# ESP32-S3-WROOM-1_Breakout.net
KiCad netlist of a schematic drawn in EasyEDA Pro
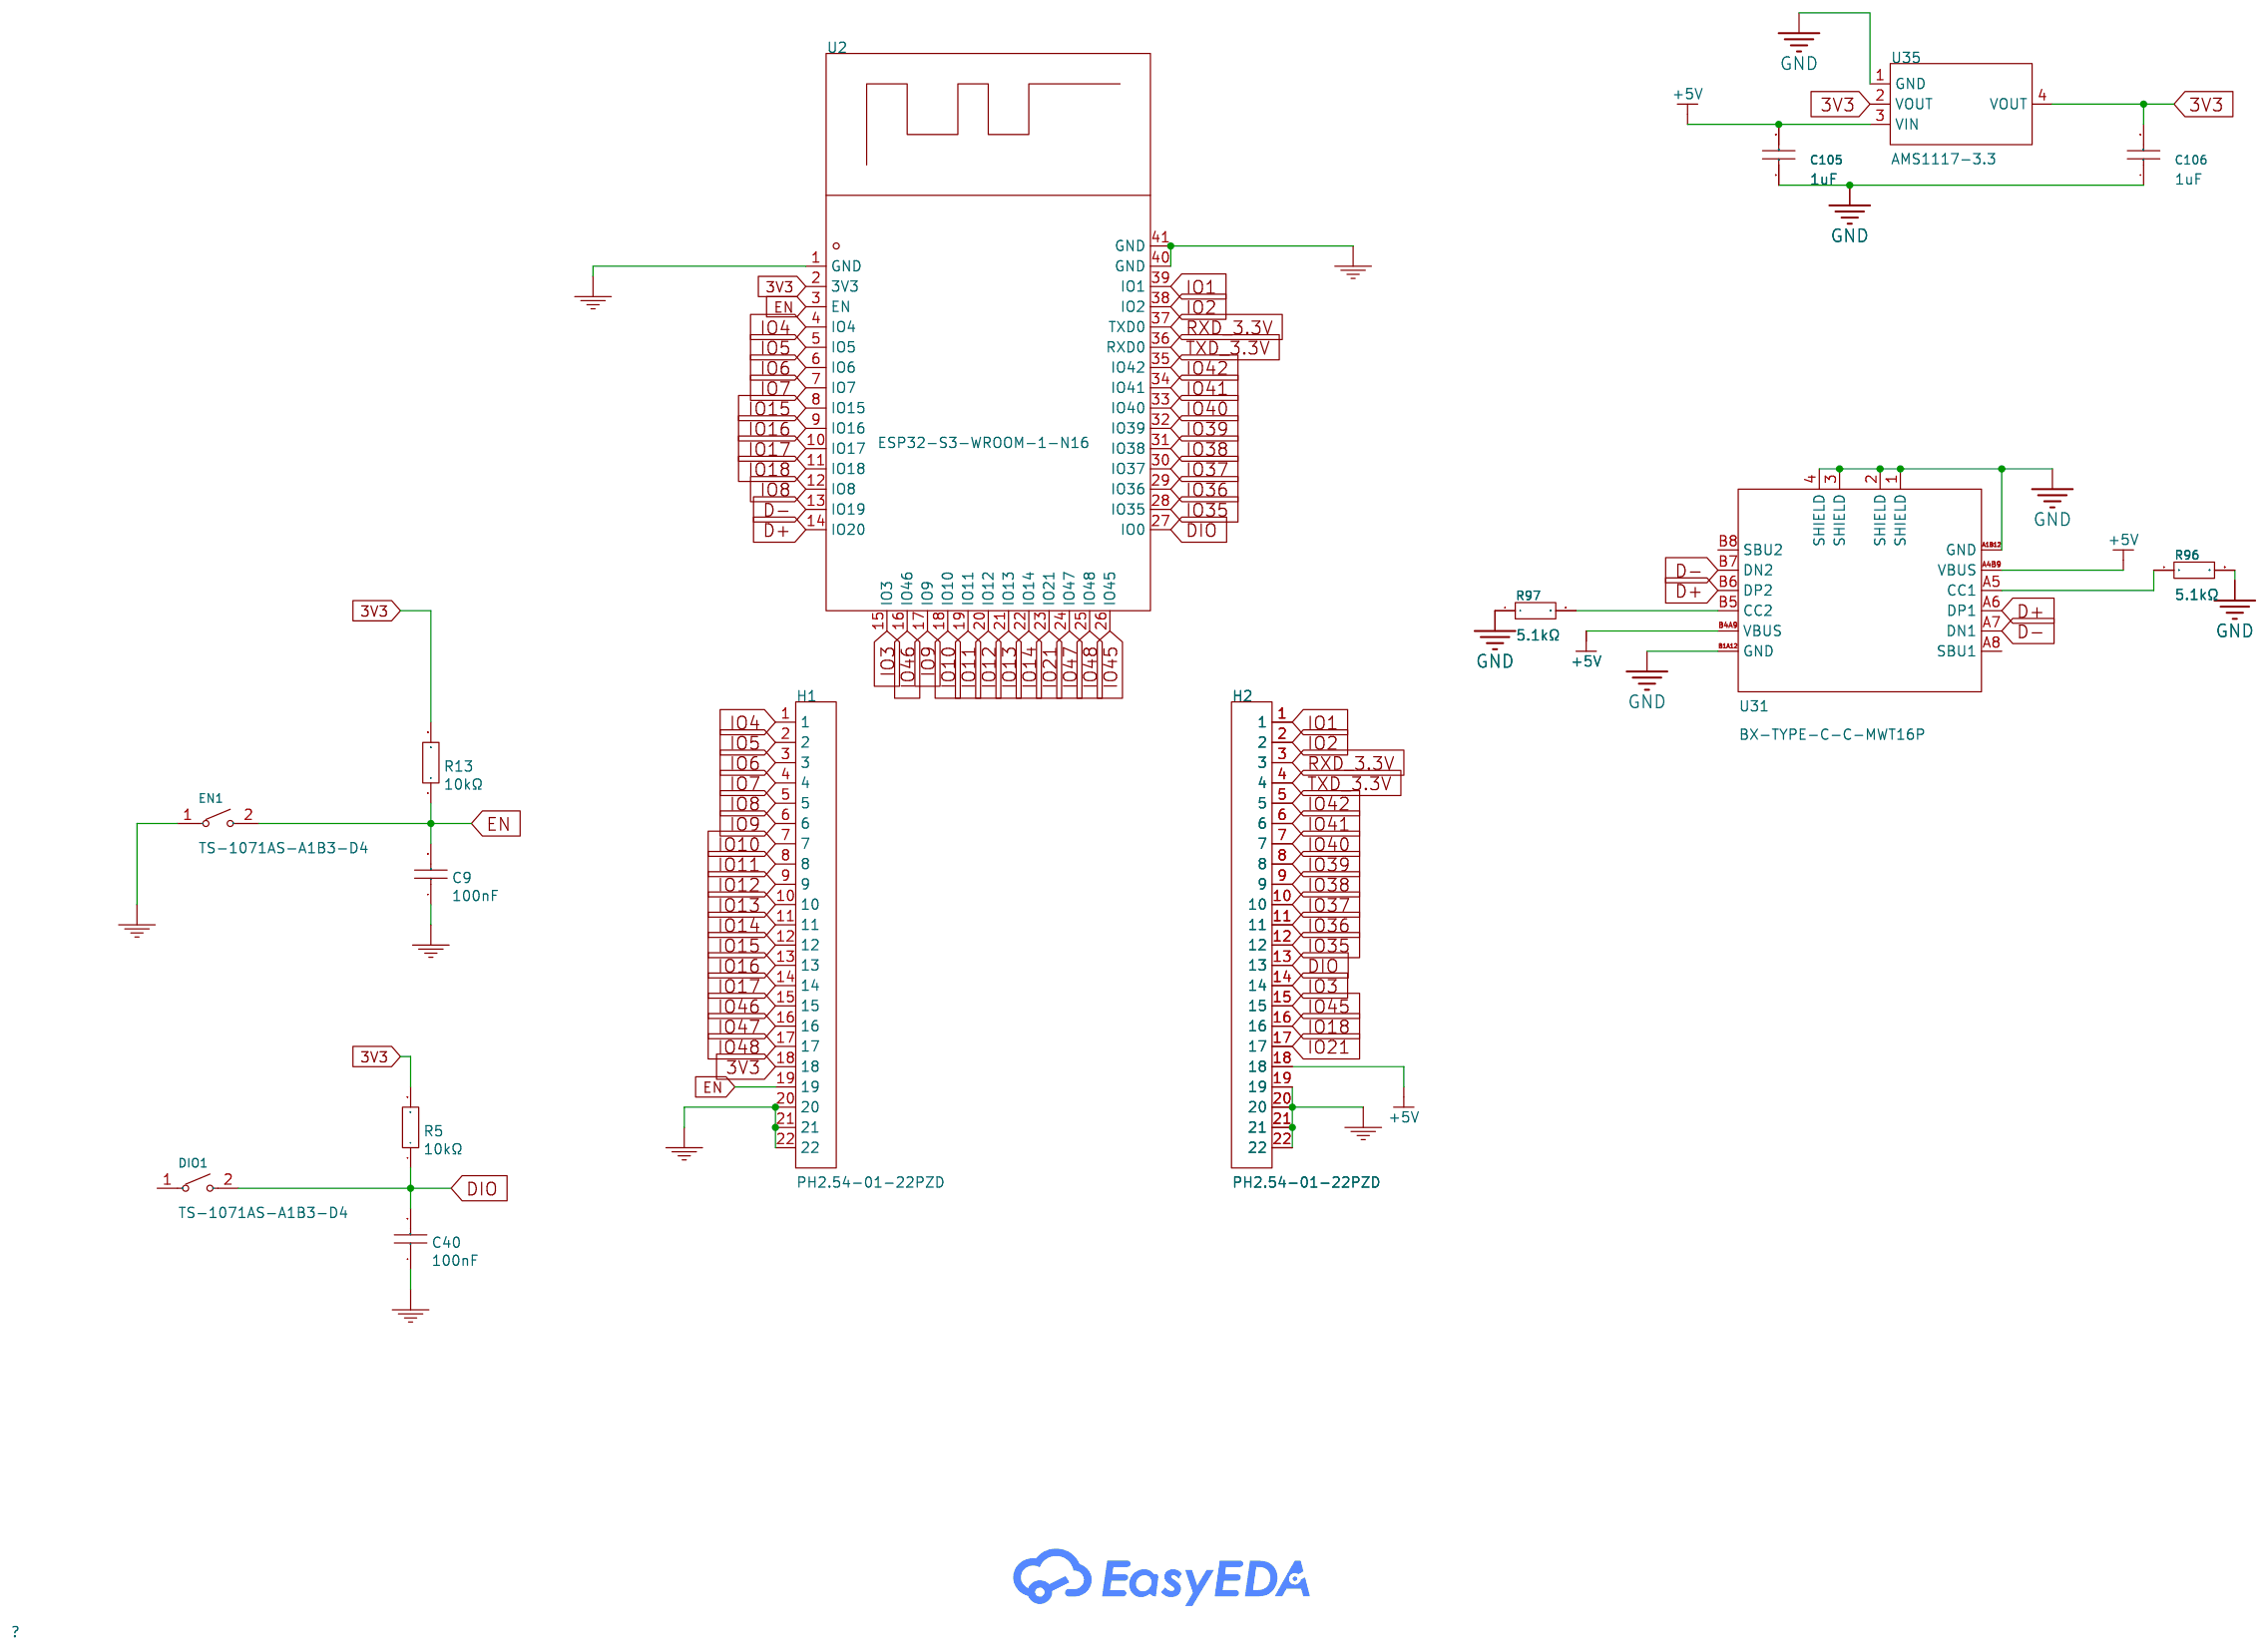
[diagram p0: schematic sheet]

(export (version "E")
  (design (tool "Eeschema 10.0.6"))
  (components
    (comp (ref "C9")
      (value "100nF")
      (footprint "easyedapro:C0402_NEW")
      (fields (field (name "Manufacturer Part") "CL05B104KO5NNNC") (field (name "Manufacturer") "SAMSUNG"))
      (libsource (lib "easyedapro") (part "100nF"))
    )
    (comp (ref "C40")
      (value "100nF")
      (footprint "easyedapro:C0402_NEW")
      (fields (field (name "Manufacturer Part") "CL05B104KO5NNNC") (field (name "Manufacturer") "SAMSUNG"))
      (libsource (lib "easyedapro") (part "100nF"))
    )
    (comp (ref "C105")
      (value "1uF")
      (footprint "easyedapro:C0402")
      (fields
        (field (name "Manufacturer Part") "CL05A105KP5NNNC")
        (field (name "Manufacturer") "SAMSUNG(三星)")
      )
      (libsource (lib "easyedapro") (part "CL05A105KP5NNNC"))
    )
    (comp (ref "C106")
      (value "1uF")
      (footprint "easyedapro:C0402")
      (fields
        (field (name "Manufacturer Part") "CL05A105KP5NNNC")
        (field (name "Manufacturer") "SAMSUNG(三星)")
      )
      (libsource (lib "easyedapro") (part "CL05A105KP5NNNC"))
    )
    (comp (ref "DIO1")
      (value "TS-1071AS-A1B3-D4")
      (footprint "easyedapro:SW-SMD_L4.0-W3.0-LS4.8")
      (fields (field (name "Manufacturer") "Yuandi(元迪)"))
      (libsource (lib "easyedapro") (part "TS-1071AS-A1B3-D4"))
    )
    (comp (ref "EN1")
      (value "TS-1071AS-A1B3-D4")
      (footprint "easyedapro:SW-SMD_L4.0-W3.0-LS4.8")
      (fields (field (name "Manufacturer") "Yuandi(元迪)"))
      (libsource (lib "easyedapro") (part "TS-1071AS-A1B3-D4"))
    )
    (comp (ref "H1")
      (value "PH2.54-01-22PZD")
      (footprint "easyedapro:HDR-TH_PH2.54-01-22PZD")
      (fields (field (name "Manufacturer") "XUNPU(讯普)"))
      (libsource (lib "easyedapro") (part "PH2.54-01-22PZD"))
    )
    (comp (ref "H2")
      (value "PH2.54-01-22PZD")
      (footprint "easyedapro:HDR-TH_PH2.54-01-22PZD")
      (fields (field (name "Manufacturer") "XUNPU(讯普)"))
      (libsource (lib "easyedapro") (part "PH2.54-01-22PZD"))
    )
    (comp (ref "R5")
      (value "10kΩ")
      (footprint "easyedapro:R0402")
      (fields (field (name "Manufacturer Part") "0402WGF1002TCE") (field (name "Manufacturer") "UniOhm"))
      (libsource (lib "easyedapro") (part "10kΩ"))
    )
    (comp (ref "R13")
      (value "10kΩ")
      (footprint "easyedapro:R0402")
      (fields (field (name "Manufacturer Part") "0402WGF1002TCE") (field (name "Manufacturer") "UniOhm"))
      (libsource (lib "easyedapro") (part "10kΩ"))
    )
    (comp (ref "R96")
      (value "5.1kΩ")
      (footprint "easyedapro:R0402")
      (fields
        (field (name "Manufacturer Part") "0402WGF5101TCE")
        (field (name "Manufacturer") "UNI-ROYAL(厚声)")
      )
      (libsource (lib "easyedapro") (part "0402WGF5101TCE"))
    )
    (comp (ref "R97")
      (value "5.1kΩ")
      (footprint "easyedapro:R0402")
      (fields
        (field (name "Manufacturer Part") "0402WGF5101TCE")
        (field (name "Manufacturer") "UNI-ROYAL(厚声)")
      )
      (libsource (lib "easyedapro") (part "0402WGF5101TCE"))
    )
    (comp (ref "U2")
      (value "ESP32-S3-WROOM-1-N16")
      (footprint "easyedapro:WIRELM-SMD_ESP32-S3-WROOM-1")
      (fields (field (name "Manufacturer") "ESPRESSIF(乐鑫)"))
      (libsource (lib "easyedapro") (part "ESP32-S3-WROOM-1(N16)"))
    )
    (comp (ref "U31")
      (value "BX-TYPE-C-C-MWT16P")
      (footprint "easyedapro:USB-C-SMD_BX-TYPE-C-C-MWT16P")
      (fields (field (name "Manufacturer") "Bossie(博锡)"))
      (libsource (lib "easyedapro") (part "BX-TYPE-C-C-MWT16P"))
    )
    (comp (ref "U35")
      (value "AMS1117-3.3")
      (footprint "easyedapro:SOT-223-3_L6.5-W3.4-P2.30-LS7.0-BR")
      (fields (field (name "Manufacturer") "AMS"))
      (libsource (lib "easyedapro") (part "AMS1117-3.3"))
    )
  )
  (nets
    (net (code "1") (name "+5V") (class "Default")
      (node (ref "C105") (pin "2") (pinfunction "2_2") (pintype "input"))
      (node (ref "H2") (pin "18") (pinfunction "18_18") (pintype "unspecified"))
      (node (ref "U31") (pin "A4B9") (pinfunction "VBUS_A4B9") (pintype "unspecified"))
      (node (ref "U31") (pin "B4A9") (pinfunction "VBUS_B4A9") (pintype "unspecified"))
      (node (ref "U35") (pin "3") (pinfunction "VIN_3") (pintype "unspecified"))
    )
    (net (code "2") (name "3V3") (class "Default")
      (node (ref "C106") (pin "2") (pinfunction "2_2") (pintype "input"))
      (node (ref "H1") (pin "18") (pinfunction "18_18") (pintype "unspecified"))
      (node (ref "R13") (pin "2") (pinfunction "2_2") (pintype "input"))
      (node (ref "R5") (pin "2") (pinfunction "2_2") (pintype "input"))
      (node (ref "U2") (pin "2") (pinfunction "3V3_2") (pintype "unspecified"))
      (node (ref "U35") (pin "2") (pinfunction "VOUT_2") (pintype "unspecified"))
      (node (ref "U35") (pin "4") (pinfunction "VOUT_4") (pintype "unspecified"))
    )
    (net (code "3") (name "D+") (class "Default")
      (node (ref "U2") (pin "14") (pinfunction "IO20_14") (pintype "unspecified"))
      (node (ref "U31") (pin "A6") (pinfunction "DP1_A6") (pintype "unspecified"))
      (node (ref "U31") (pin "B6") (pinfunction "DP2_B6") (pintype "unspecified"))
    )
    (net (code "4") (name "D-") (class "Default")
      (node (ref "U2") (pin "13") (pinfunction "IO19_13") (pintype "unspecified"))
      (node (ref "U31") (pin "A7") (pinfunction "DN1_A7") (pintype "unspecified"))
      (node (ref "U31") (pin "B7") (pinfunction "DN2_B7") (pintype "unspecified"))
    )
    (net (code "5") (name "DIO") (class "Default")
      (node (ref "C40") (pin "2") (pinfunction "2_2") (pintype "input"))
      (node (ref "DIO1") (pin "2") (pinfunction "2_2") (pintype "input"))
      (node (ref "H2") (pin "13") (pinfunction "13_13") (pintype "unspecified"))
      (node (ref "R5") (pin "1") (pinfunction "1_1") (pintype "input"))
      (node (ref "U2") (pin "27") (pinfunction "IO0_27") (pintype "unspecified"))
    )
    (net (code "6") (name "EN") (class "Default")
      (node (ref "C9") (pin "2") (pinfunction "2_2") (pintype "input"))
      (node (ref "EN1") (pin "2") (pinfunction "2_2") (pintype "input"))
      (node (ref "H1") (pin "19") (pinfunction "19_19") (pintype "unspecified"))
      (node (ref "R13") (pin "1") (pinfunction "1_1") (pintype "input"))
      (node (ref "U2") (pin "3") (pinfunction "EN_3") (pintype "unspecified"))
    )
    (net (code "7") (name "GND") (class "Default")
      (node (ref "C105") (pin "1") (pinfunction "1_1") (pintype "input"))
      (node (ref "C106") (pin "1") (pinfunction "1_1") (pintype "input"))
      (node (ref "C40") (pin "1") (pinfunction "1_1") (pintype "input"))
      (node (ref "C9") (pin "1") (pinfunction "1_1") (pintype "input"))
      (node (ref "EN1") (pin "1") (pinfunction "1_1") (pintype "input"))
      (node (ref "H1") (pin "20") (pinfunction "20_20") (pintype "unspecified"))
      (node (ref "H1") (pin "21") (pinfunction "21_21") (pintype "unspecified"))
      (node (ref "H1") (pin "22") (pinfunction "22_22") (pintype "unspecified"))
      (node (ref "H2") (pin "19") (pinfunction "19_19") (pintype "unspecified"))
      (node (ref "H2") (pin "20") (pinfunction "20_20") (pintype "unspecified"))
      (node (ref "H2") (pin "21") (pinfunction "21_21") (pintype "unspecified"))
      (node (ref "H2") (pin "22") (pinfunction "22_22") (pintype "unspecified"))
      (node (ref "R96") (pin "2") (pinfunction "2_2") (pintype "input"))
      (node (ref "R97") (pin "1") (pinfunction "1_1") (pintype "input"))
      (node (ref "U2") (pin "1") (pinfunction "GND_1") (pintype "unspecified"))
      (node (ref "U2") (pin "40") (pinfunction "GND_40") (pintype "unspecified"))
      (node (ref "U2") (pin "41") (pinfunction "GND_41") (pintype "unspecified"))
      (node (ref "U31") (pin "1") (pinfunction "SHIELD_1") (pintype "unspecified"))
      (node (ref "U31") (pin "2") (pinfunction "SHIELD_2") (pintype "unspecified"))
      (node (ref "U31") (pin "3") (pinfunction "SHIELD_3") (pintype "unspecified"))
      (node (ref "U31") (pin "4") (pinfunction "SHIELD_4") (pintype "unspecified"))
      (node (ref "U31") (pin "A1B12") (pinfunction "GND_A1B12") (pintype "unspecified"))
      (node (ref "U31") (pin "B1A12") (pinfunction "GND_B1A12") (pintype "unspecified"))
      (node (ref "U35") (pin "1") (pinfunction "GND_1") (pintype "unspecified"))
    )
    (net (code "8") (name "IO1") (class "Default")
      (node (ref "H2") (pin "1") (pinfunction "1_1") (pintype "unspecified"))
      (node (ref "U2") (pin "39") (pinfunction "IO1_39") (pintype "unspecified"))
    )
    (net (code "9") (name "IO2") (class "Default")
      (node (ref "H2") (pin "2") (pinfunction "2_2") (pintype "unspecified"))
      (node (ref "U2") (pin "38") (pinfunction "IO2_38") (pintype "unspecified"))
    )
    (net (code "10") (name "IO3") (class "Default")
      (node (ref "H2") (pin "14") (pinfunction "14_14") (pintype "unspecified"))
      (node (ref "U2") (pin "15") (pinfunction "IO3_15") (pintype "unspecified"))
    )
    (net (code "11") (name "IO4") (class "Default")
      (node (ref "H1") (pin "1") (pinfunction "1_1") (pintype "unspecified"))
      (node (ref "U2") (pin "4") (pinfunction "IO4_4") (pintype "unspecified"))
    )
    (net (code "12") (name "IO5") (class "Default")
      (node (ref "H1") (pin "2") (pinfunction "2_2") (pintype "unspecified"))
      (node (ref "U2") (pin "5") (pinfunction "IO5_5") (pintype "unspecified"))
    )
    (net (code "13") (name "IO6") (class "Default")
      (node (ref "H1") (pin "3") (pinfunction "3_3") (pintype "unspecified"))
      (node (ref "U2") (pin "6") (pinfunction "IO6_6") (pintype "unspecified"))
    )
    (net (code "14") (name "IO7") (class "Default")
      (node (ref "H1") (pin "4") (pinfunction "4_4") (pintype "unspecified"))
      (node (ref "U2") (pin "7") (pinfunction "IO7_7") (pintype "unspecified"))
    )
    (net (code "15") (name "IO8") (class "Default")
      (node (ref "H1") (pin "5") (pinfunction "5_5") (pintype "unspecified"))
      (node (ref "U2") (pin "12") (pinfunction "IO8_12") (pintype "unspecified"))
    )
    (net (code "16") (name "IO9") (class "Default")
      (node (ref "H1") (pin "6") (pinfunction "6_6") (pintype "unspecified"))
      (node (ref "U2") (pin "17") (pinfunction "IO9_17") (pintype "unspecified"))
    )
    (net (code "17") (name "IO10") (class "Default")
      (node (ref "H1") (pin "7") (pinfunction "7_7") (pintype "unspecified"))
      (node (ref "U2") (pin "18") (pinfunction "IO10_18") (pintype "unspecified"))
    )
    (net (code "18") (name "IO11") (class "Default")
      (node (ref "H1") (pin "8") (pinfunction "8_8") (pintype "unspecified"))
      (node (ref "U2") (pin "19") (pinfunction "IO11_19") (pintype "unspecified"))
    )
    (net (code "19") (name "IO12") (class "Default")
      (node (ref "H1") (pin "9") (pinfunction "9_9") (pintype "unspecified"))
      (node (ref "U2") (pin "20") (pinfunction "IO12_20") (pintype "unspecified"))
    )
    (net (code "20") (name "IO13") (class "Default")
      (node (ref "H1") (pin "10") (pinfunction "10_10") (pintype "unspecified"))
      (node (ref "U2") (pin "21") (pinfunction "IO13_21") (pintype "unspecified"))
    )
    (net (code "21") (name "IO14") (class "Default")
      (node (ref "H1") (pin "11") (pinfunction "11_11") (pintype "unspecified"))
      (node (ref "U2") (pin "22") (pinfunction "IO14_22") (pintype "unspecified"))
    )
    (net (code "22") (name "IO15") (class "Default")
      (node (ref "H1") (pin "12") (pinfunction "12_12") (pintype "unspecified"))
      (node (ref "U2") (pin "8") (pinfunction "IO15_8") (pintype "unspecified"))
    )
    (net (code "23") (name "IO16") (class "Default")
      (node (ref "H1") (pin "13") (pinfunction "13_13") (pintype "unspecified"))
      (node (ref "U2") (pin "9") (pinfunction "IO16_9") (pintype "unspecified"))
    )
    (net (code "24") (name "IO17") (class "Default")
      (node (ref "H1") (pin "14") (pinfunction "14_14") (pintype "unspecified"))
      (node (ref "U2") (pin "10") (pinfunction "IO17_10") (pintype "unspecified"))
    )
    (net (code "25") (name "IO18") (class "Default")
      (node (ref "H2") (pin "16") (pinfunction "16_16") (pintype "unspecified"))
      (node (ref "U2") (pin "11") (pinfunction "IO18_11") (pintype "unspecified"))
    )
    (net (code "26") (name "IO21") (class "Default")
      (node (ref "H2") (pin "17") (pinfunction "17_17") (pintype "unspecified"))
      (node (ref "U2") (pin "23") (pinfunction "IO21_23") (pintype "unspecified"))
    )
    (net (code "27") (name "IO35") (class "Default")
      (node (ref "H2") (pin "12") (pinfunction "12_12") (pintype "unspecified"))
      (node (ref "U2") (pin "28") (pinfunction "IO35_28") (pintype "unspecified"))
    )
    (net (code "28") (name "IO36") (class "Default")
      (node (ref "H2") (pin "11") (pinfunction "11_11") (pintype "unspecified"))
      (node (ref "U2") (pin "29") (pinfunction "IO36_29") (pintype "unspecified"))
    )
    (net (code "29") (name "IO37") (class "Default")
      (node (ref "H2") (pin "10") (pinfunction "10_10") (pintype "unspecified"))
      (node (ref "U2") (pin "30") (pinfunction "IO37_30") (pintype "unspecified"))
    )
    (net (code "30") (name "IO38") (class "Default")
      (node (ref "H2") (pin "9") (pinfunction "9_9") (pintype "unspecified"))
      (node (ref "U2") (pin "31") (pinfunction "IO38_31") (pintype "unspecified"))
    )
    (net (code "31") (name "IO39") (class "Default")
      (node (ref "H2") (pin "8") (pinfunction "8_8") (pintype "unspecified"))
      (node (ref "U2") (pin "32") (pinfunction "IO39_32") (pintype "unspecified"))
    )
    (net (code "32") (name "IO40") (class "Default")
      (node (ref "H2") (pin "7") (pinfunction "7_7") (pintype "unspecified"))
      (node (ref "U2") (pin "33") (pinfunction "IO40_33") (pintype "unspecified"))
    )
    (net (code "33") (name "IO41") (class "Default")
      (node (ref "H2") (pin "6") (pinfunction "6_6") (pintype "unspecified"))
      (node (ref "U2") (pin "34") (pinfunction "IO41_34") (pintype "unspecified"))
    )
    (net (code "34") (name "IO42") (class "Default")
      (node (ref "H2") (pin "5") (pinfunction "5_5") (pintype "unspecified"))
      (node (ref "U2") (pin "35") (pinfunction "IO42_35") (pintype "unspecified"))
    )
    (net (code "35") (name "IO45") (class "Default")
      (node (ref "H2") (pin "15") (pinfunction "15_15") (pintype "unspecified"))
      (node (ref "U2") (pin "26") (pinfunction "IO45_26") (pintype "unspecified"))
    )
    (net (code "36") (name "IO46") (class "Default")
      (node (ref "H1") (pin "15") (pinfunction "15_15") (pintype "unspecified"))
      (node (ref "U2") (pin "16") (pinfunction "IO46_16") (pintype "unspecified"))
    )
    (net (code "37") (name "IO47") (class "Default")
      (node (ref "H1") (pin "16") (pinfunction "16_16") (pintype "unspecified"))
      (node (ref "U2") (pin "24") (pinfunction "IO47_24") (pintype "unspecified"))
    )
    (net (code "38") (name "IO48") (class "Default")
      (node (ref "H1") (pin "17") (pinfunction "17_17") (pintype "unspecified"))
      (node (ref "U2") (pin "25") (pinfunction "IO48_25") (pintype "unspecified"))
    )
    (net (code "39") (name "Net-(U31-CC1)") (class "Default")
      (node (ref "R96") (pin "1") (pinfunction "1_1") (pintype "input"))
      (node (ref "U31") (pin "A5") (pinfunction "CC1_A5") (pintype "unspecified"))
    )
    (net (code "40") (name "Net-(U31-CC2)") (class "Default")
      (node (ref "R97") (pin "2") (pinfunction "2_2") (pintype "input"))
      (node (ref "U31") (pin "B5") (pinfunction "CC2_B5") (pintype "unspecified"))
    )
    (net (code "41") (name "RXD_3.3V") (class "Default")
      (node (ref "H2") (pin "3") (pinfunction "3_3") (pintype "unspecified"))
      (node (ref "U2") (pin "37") (pinfunction "TXD0_37") (pintype "unspecified"))
    )
    (net (code "42") (name "TXD_3.3V") (class "Default")
      (node (ref "H2") (pin "4") (pinfunction "4_4") (pintype "unspecified"))
      (node (ref "U2") (pin "36") (pinfunction "RXD0_36") (pintype "unspecified"))
    )
    (net (code "43") (name "unconnected-(DIO1-Pad1)") (class "Default")
      (node (ref "DIO1") (pin "1") (pinfunction "1_1") (pintype "input"))
    )
    (net (code "44") (name "unconnected-(U31-SBU1-PadA8)") (class "Default")
      (node (ref "U31") (pin "A8") (pinfunction "SBU1_A8") (pintype "unspecified"))
    )
    (net (code "45") (name "unconnected-(U31-SBU2-PadB8)") (class "Default")
      (node (ref "U31") (pin "B8") (pinfunction "SBU2_B8") (pintype "unspecified"))
    )
  )
)
